# Sheet1.net
KiCad netlist of a schematic drawn in Altium Designer
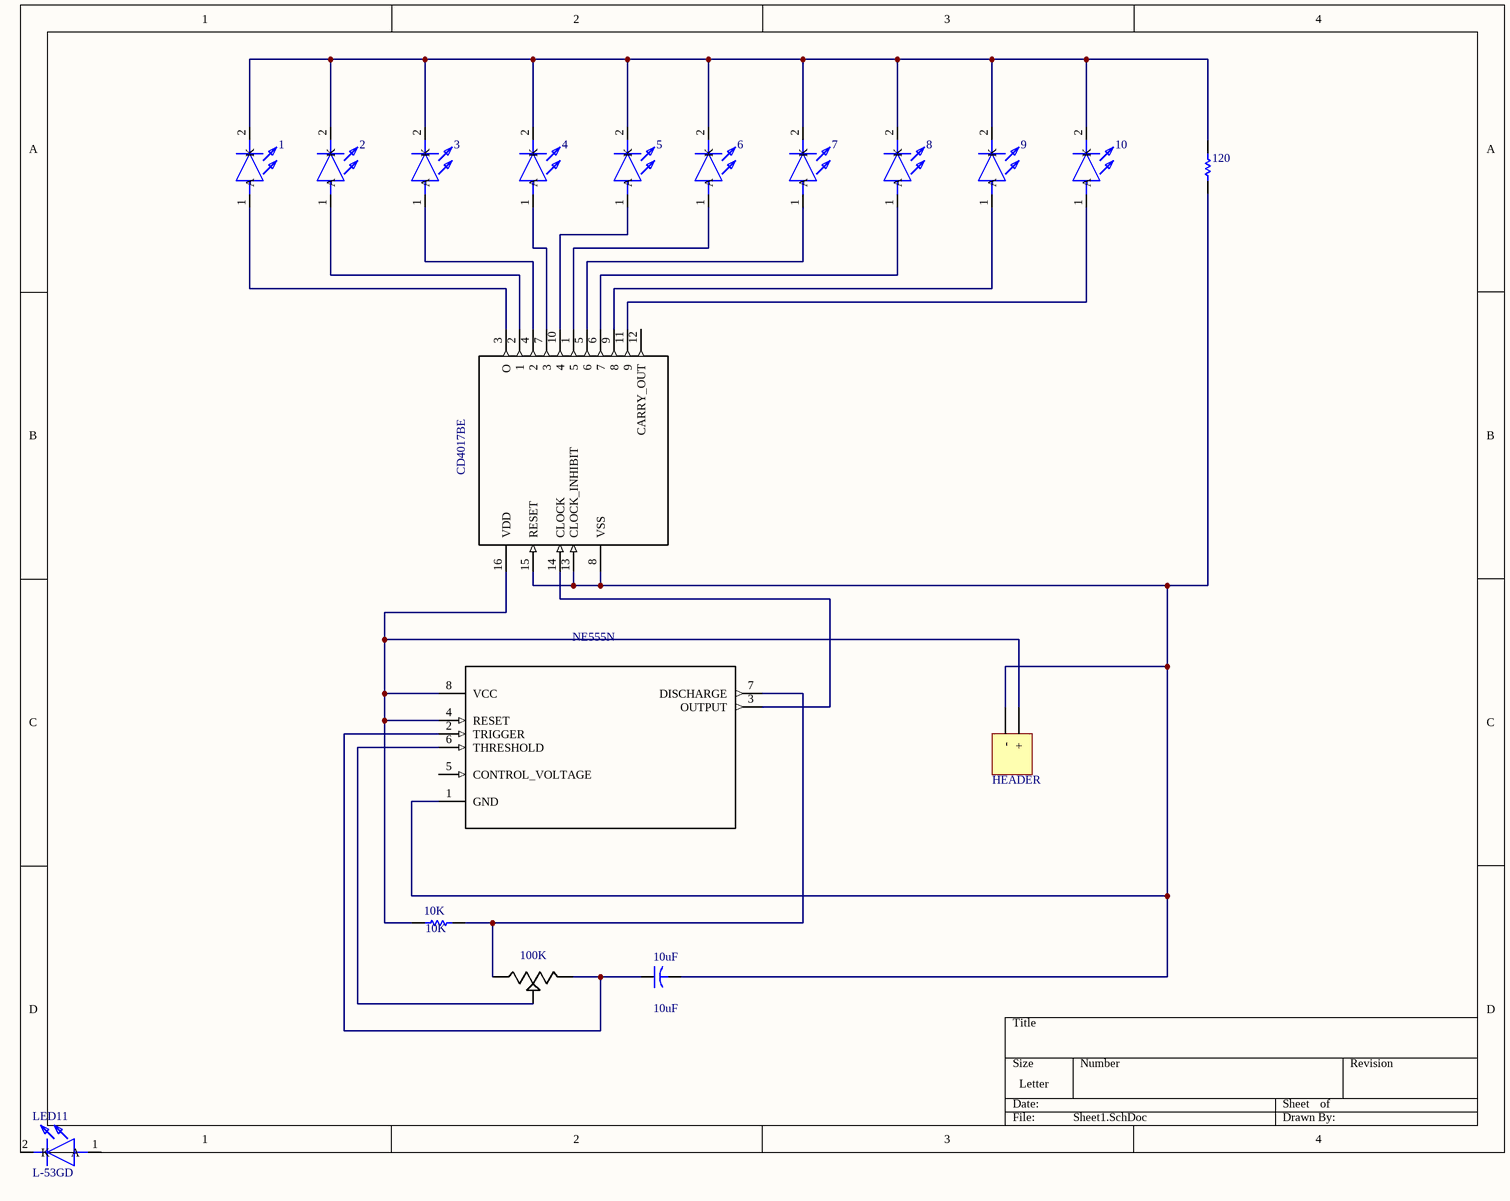
[diagram p0: Sheet1.SchDoc]

(export (version "E")
  (design (tool "Eeschema 10.0.6"))
  (components
    (comp (ref "1")
      (value "1")
      (footprint "SamacSys:L-53GD")
      (description "LED")
      (fields (field (name "MANUFACTURER_PART_NUMBER") "L-53GD") (field (name "RS PART NUMBER") "2286004A"))
      (libsource (lib "SamacSys") (part "L-53GD"))
    )
    (comp (ref "2")
      (value "1")
      (footprint "SamacSys:L-53GD")
      (description "LED")
      (fields (field (name "MANUFACTURER_PART_NUMBER") "L-53GD") (field (name "RS PART NUMBER") "2286004A"))
      (libsource (lib "SamacSys") (part "L-53GD"))
    )
    (comp (ref "3")
      (value "3")
      (footprint "SamacSys:L-53GD")
      (description "LED")
      (fields (field (name "MANUFACTURER_PART_NUMBER") "L-53GD") (field (name "RS PART NUMBER") "2286004A"))
      (libsource (lib "SamacSys") (part "L-53GD"))
    )
    (comp (ref "4")
      (value "4")
      (footprint "SamacSys:L-53GD")
      (description "LED")
      (fields (field (name "MANUFACTURER_PART_NUMBER") "L-53GD") (field (name "RS PART NUMBER") "2286004A"))
      (libsource (lib "SamacSys") (part "L-53GD"))
    )
    (comp (ref "5")
      (value "5")
      (footprint "SamacSys:L-53GD")
      (description "LED")
      (fields (field (name "MANUFACTURER_PART_NUMBER") "L-53GD") (field (name "RS PART NUMBER") "2286004A"))
      (libsource (lib "SamacSys") (part "L-53GD"))
    )
    (comp (ref "6")
      (value "6")
      (footprint "SamacSys:L-53GD")
      (description "LED")
      (fields (field (name "MANUFACTURER_PART_NUMBER") "L-53GD") (field (name "RS PART NUMBER") "2286004A"))
      (libsource (lib "SamacSys") (part "L-53GD"))
    )
    (comp (ref "7")
      (value "7")
      (footprint "SamacSys:L-53GD")
      (description "LED")
      (fields (field (name "MANUFACTURER_PART_NUMBER") "L-53GD") (field (name "RS PART NUMBER") "2286004A"))
      (libsource (lib "SamacSys") (part "L-53GD"))
    )
    (comp (ref "8")
      (value "8")
      (footprint "SamacSys:L-53GD")
      (description "LED")
      (fields (field (name "MANUFACTURER_PART_NUMBER") "L-53GD") (field (name "RS PART NUMBER") "2286004A"))
      (libsource (lib "SamacSys") (part "L-53GD"))
    )
    (comp (ref "9")
      (value "9")
      (footprint "SamacSys:L-53GD")
      (description "LED")
      (fields (field (name "MANUFACTURER_PART_NUMBER") "L-53GD") (field (name "RS PART NUMBER") "2286004A"))
      (libsource (lib "SamacSys") (part "L-53GD"))
    )
    (comp (ref "10")
      (value "10")
      (footprint "SamacSys:L-53GD")
      (description "LED")
      (fields (field (name "MANUFACTURER_PART_NUMBER") "L-53GD") (field (name "RS PART NUMBER") "2286004A"))
      (libsource (lib "SamacSys") (part "L-53GD"))
    )
    (comp (ref "10K")
      (value "10K")
      (footprint "AXIAL-0.3")
      (description "Resistor")
      (fields (field (name "Comment") "Res1") (field (name "PUBLISHER") "Altium Limited"))
      (libsource (lib "Miscellaneous Devices") (part "Res1"))
    )
    (comp (ref "10uF")
      (value "10uF")
      (footprint "CAPR5-4X5")
      (description "Capacitor")
      (fields (field (name "Comment") "Cap2") (field (name "PUBLISHER") "Altium Limited"))
      (libsource (lib "Miscellaneous Devices") (part "Cap2"))
    )
    (comp (ref "100K")
      (value "100K")
      (footprint "*TRIM_EVN-D8AA03B14")
      (description "Trimmer; Carbon; Rest 10 Kilohms; PCB; 1 Turn; Pwr-Rtg 0.1 W; Linear; Top Adj; 6 mm SQ")
      (fields (field (name "MF") "Panasonic Electronic") (field (name "MP") "EVN-D8AA03B14"))
      (libsource (lib "EVN-D8AA03B14") (part "EVN-D8AA03B14"))
    )
    (comp (ref "120")
      (value "120")
      (footprint "AXIAL-0.3")
      (description "Resistor")
      (fields (field (name "PUBLISHER") "Altium Limited"))
      (libsource (lib "Miscellaneous Devices") (part "Res1"))
    )
    (comp (ref "CD4017BE")
      (value "CD4017BE")
      (footprint "*DIP254P762X508-16")
      (description "IC Mos 4017/CD4017BE HARRIS")
      (fields (field (name "MF") "Texas"))
      (libsource (lib "CD4017BE") (part "CD4017BE"))
    )
    (comp (ref "HEADER")
      (value "Header 2")
      (footprint "HDR1X2")
      (description "Header, 2-Pin")
      (fields (field (name "PUBLISHER") "Altium Limited"))
      (libsource (lib "Miscellaneous Connectors") (part "Header 2"))
    )
    (comp (ref "LED11")
      (value "L-53GD")
      (footprint "SamacSys:L-53GD")
      (description "LED")
      (fields (field (name "RS PART NUMBER") "2286004A"))
      (libsource (lib "*") (part "L-53GD"))
    )
    (comp (ref "NE555N")
      (value "NE555N")
      (footprint "*DIP254P762X533-8")
      (fields (field (name "MF") "ON Semiconductor"))
      (libsource (lib "NE555N") (part "NE555N"))
    )
  )
  (nets
    (net (code "1") (name "Net-(1-A)") (class "Default")
      (node (ref "1") (pin "1") (pinfunction "A_1") (pintype "passive"))
      (node (ref "CD4017BE") (pin "3") (pinfunction "O_3") (pintype "output"))
    )
    (net (code "2") (name "Net-(1-K)") (class "Default")
      (node (ref "1") (pin "2") (pinfunction "K_2") (pintype "passive"))
      (node (ref "10") (pin "2") (pinfunction "K_2") (pintype "passive"))
      (node (ref "120") (pin "1") (pinfunction "1_1") (pintype "passive"))
      (node (ref "2") (pin "2") (pinfunction "K_2") (pintype "passive"))
      (node (ref "3") (pin "2") (pinfunction "K_2") (pintype "passive"))
      (node (ref "4") (pin "2") (pinfunction "K_2") (pintype "passive"))
      (node (ref "5") (pin "2") (pinfunction "K_2") (pintype "passive"))
      (node (ref "6") (pin "2") (pinfunction "K_2") (pintype "passive"))
      (node (ref "7") (pin "2") (pinfunction "K_2") (pintype "passive"))
      (node (ref "8") (pin "2") (pinfunction "K_2") (pintype "passive"))
      (node (ref "9") (pin "2") (pinfunction "K_2") (pintype "passive"))
    )
    (net (code "3") (name "Net-(2-A)") (class "Default")
      (node (ref "2") (pin "1") (pinfunction "A_1") (pintype "passive"))
      (node (ref "CD4017BE") (pin "2") (pinfunction "1_2") (pintype "output"))
    )
    (net (code "4") (name "Net-(3-A)") (class "Default")
      (node (ref "3") (pin "1") (pinfunction "A_1") (pintype "passive"))
      (node (ref "CD4017BE") (pin "4") (pinfunction "2_4") (pintype "output"))
    )
    (net (code "5") (name "Net-(4-A)") (class "Default")
      (node (ref "4") (pin "1") (pinfunction "A_1") (pintype "passive"))
      (node (ref "CD4017BE") (pin "7") (pinfunction "3_7") (pintype "output"))
    )
    (net (code "6") (name "Net-(5-A)") (class "Default")
      (node (ref "5") (pin "1") (pinfunction "A_1") (pintype "passive"))
      (node (ref "CD4017BE") (pin "10") (pinfunction "4_10") (pintype "output"))
    )
    (net (code "7") (name "Net-(6-A)") (class "Default")
      (node (ref "6") (pin "1") (pinfunction "A_1") (pintype "passive"))
      (node (ref "CD4017BE") (pin "1") (pinfunction "5_1") (pintype "output"))
    )
    (net (code "8") (name "Net-(7-A)") (class "Default")
      (node (ref "7") (pin "1") (pinfunction "A_1") (pintype "passive"))
      (node (ref "CD4017BE") (pin "5") (pinfunction "6_5") (pintype "output"))
    )
    (net (code "9") (name "Net-(8-A)") (class "Default")
      (node (ref "8") (pin "1") (pinfunction "A_1") (pintype "passive"))
      (node (ref "CD4017BE") (pin "6") (pinfunction "7_6") (pintype "output"))
    )
    (net (code "10") (name "Net-(9-A)") (class "Default")
      (node (ref "9") (pin "1") (pinfunction "A_1") (pintype "passive"))
      (node (ref "CD4017BE") (pin "9") (pinfunction "8_9") (pintype "output"))
    )
    (net (code "11") (name "Net-(10-A)") (class "Default")
      (node (ref "10") (pin "1") (pinfunction "A_1") (pintype "passive"))
      (node (ref "CD4017BE") (pin "11") (pinfunction "9_11") (pintype "output"))
    )
    (net (code "12") (name "Net-(CD4017BE-CLOCK)") (class "Default")
      (node (ref "CD4017BE") (pin "14") (pinfunction "CLOCK_14") (pintype "input"))
      (node (ref "NE555N") (pin "3") (pinfunction "OUTPUT_3") (pintype "output"))
    )
    (net (code "13") (name "Net-(CD4017BE-CLOCK_INHIBIT)") (class "Default")
      (node (ref "10uF") (pin "2") (pinfunction "2_2") (pintype "passive"))
      (node (ref "120") (pin "2") (pinfunction "2_2") (pintype "passive"))
      (node (ref "CD4017BE") (pin "13") (pinfunction "CLOCK_INHIBIT_13") (pintype "input"))
      (node (ref "CD4017BE") (pin "15") (pinfunction "RESET_15") (pintype "input"))
      (node (ref "CD4017BE") (pin "8") (pinfunction "VSS_8") (pintype "power_in"))
      (node (ref "HEADER") (pin "2") (pinfunction "-_2") (pintype "passive"))
      (node (ref "NE555N") (pin "1") (pinfunction "GND_1") (pintype "passive"))
    )
    (net (code "14") (name "Net-(CD4017BE-VDD)") (class "Default")
      (node (ref "10K") (pin "1") (pinfunction "1_1") (pintype "passive"))
      (node (ref "CD4017BE") (pin "16") (pinfunction "VDD_16") (pintype "power_in"))
      (node (ref "HEADER") (pin "1") (pinfunction "+_1") (pintype "passive"))
      (node (ref "NE555N") (pin "4") (pinfunction "RESET_4") (pintype "input"))
      (node (ref "NE555N") (pin "8") (pinfunction "VCC_8") (pintype "power_in"))
    )
    (net (code "15") (name "Net-(NE555N-DISCHARGE)") (class "Default")
      (node (ref "100K") (pin "1") (pinfunction "1_1") (pintype "passive"))
      (node (ref "10K") (pin "2") (pinfunction "2_2") (pintype "passive"))
      (node (ref "NE555N") (pin "7") (pinfunction "DISCHARGE_7") (pintype "output"))
    )
    (net (code "16") (name "Net-(NE555N-THRESHOLD)") (class "Default")
      (node (ref "100K") (pin "2") (pinfunction "2_2") (pintype "passive"))
      (node (ref "NE555N") (pin "6") (pinfunction "THRESHOLD_6") (pintype "input"))
    )
    (net (code "17") (name "Net-(NE555N-TRIGGER)") (class "Default")
      (node (ref "100K") (pin "3") (pinfunction "3_3") (pintype "passive"))
      (node (ref "10uF") (pin "1") (pinfunction "1_1") (pintype "passive"))
      (node (ref "NE555N") (pin "2") (pinfunction "TRIGGER_2") (pintype "input"))
    )
    (net (code "18") (name "unconnected-(CD4017BE-CARRY_OUT-Pad12)") (class "Default")
      (node (ref "CD4017BE") (pin "12") (pinfunction "CARRY_OUT_12") (pintype "output"))
    )
    (net (code "19") (name "unconnected-(LED11-A-Pad1)") (class "Default")
      (node (ref "LED11") (pin "1") (pinfunction "A_1") (pintype "passive"))
    )
    (net (code "20") (name "unconnected-(LED11-K-Pad2)") (class "Default")
      (node (ref "LED11") (pin "2") (pinfunction "K_2") (pintype "passive"))
    )
    (net (code "21") (name "unconnected-(NE555N-CONTROL_VOLTAGE-Pad5)") (class "Default")
      (node (ref "NE555N") (pin "5") (pinfunction "CONTROL_VOLTAGE_5") (pintype "input"))
    )
  )
)
